# powerlolu.net
KiCad netlist of a schematic drawn in EAGLE
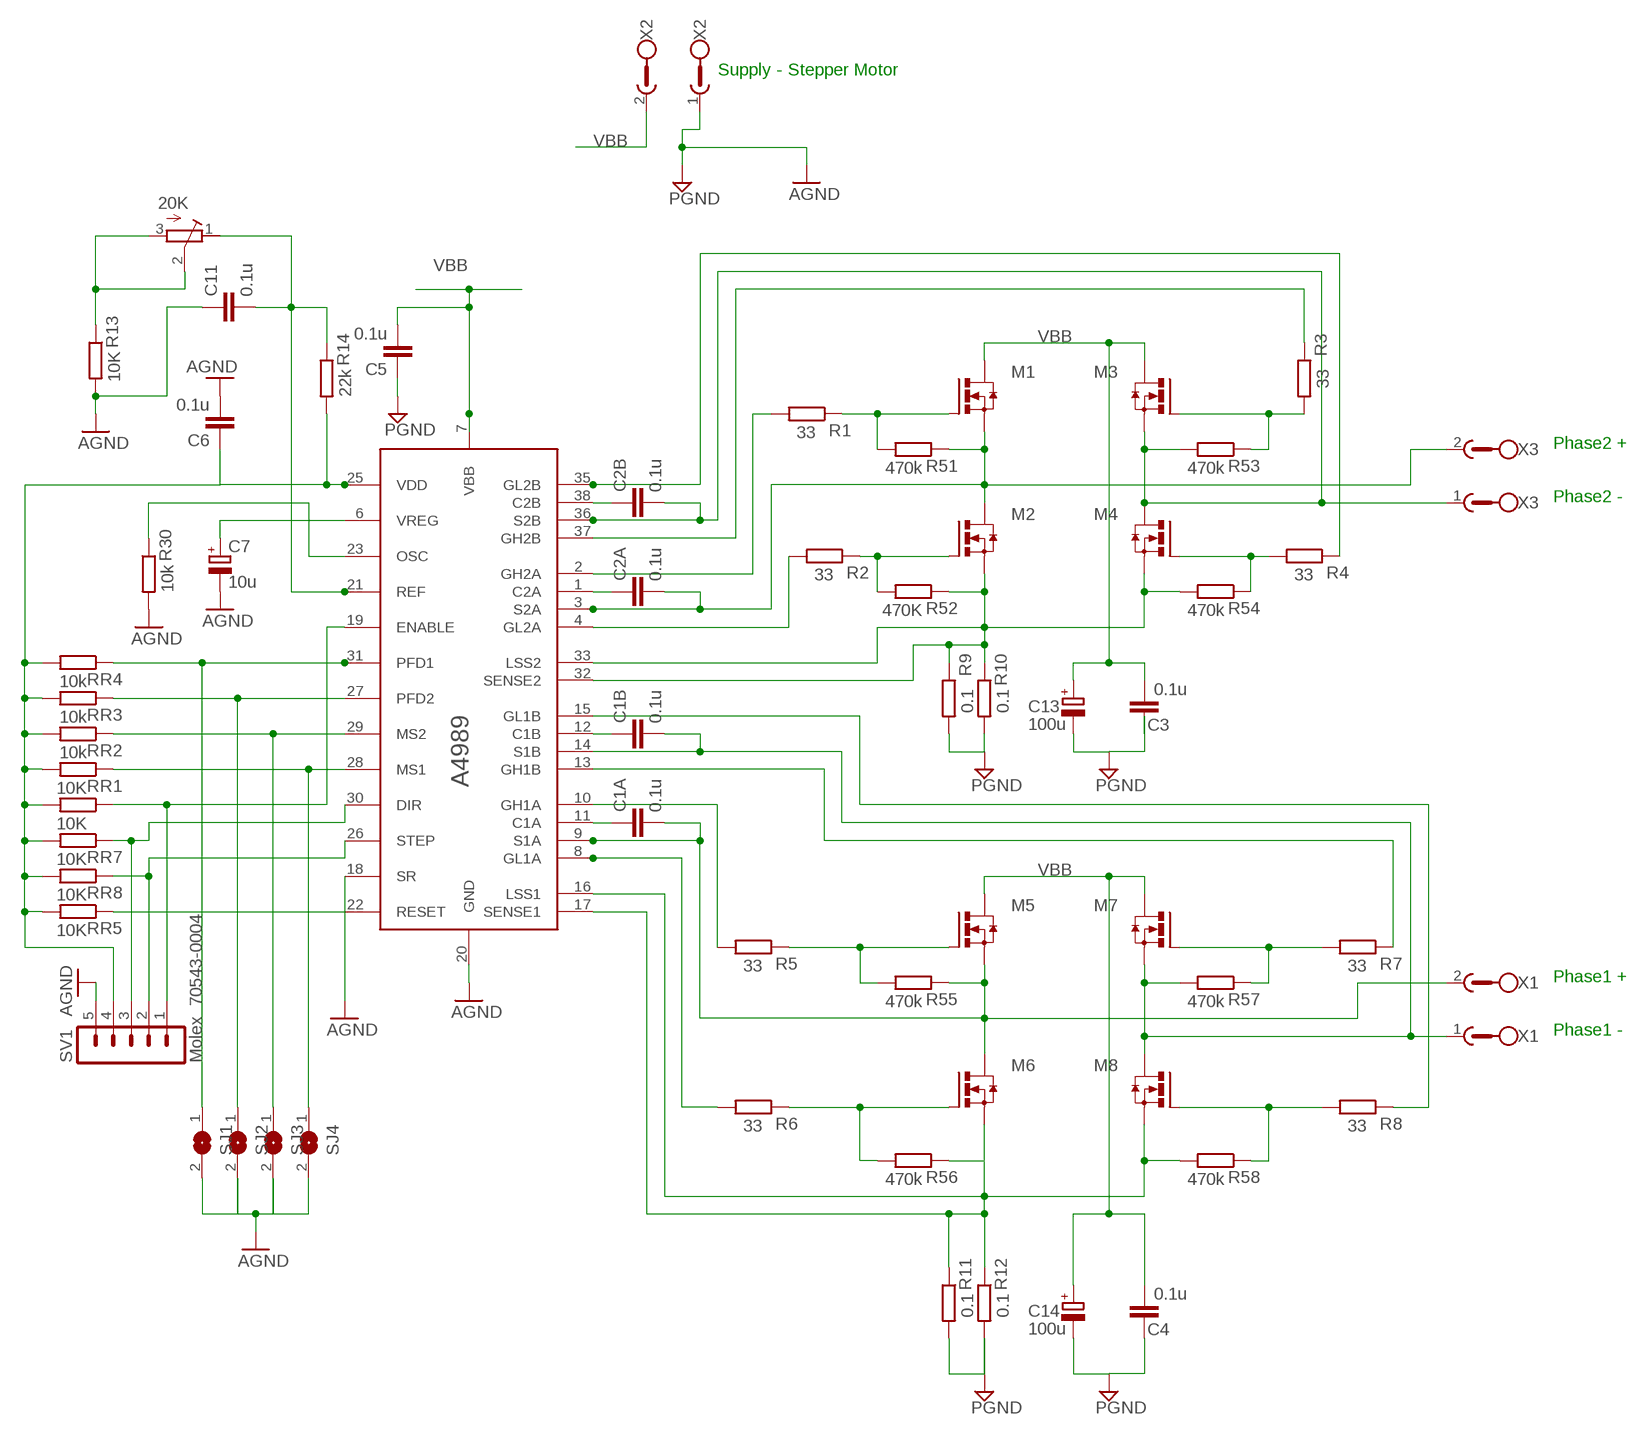
[diagram p0: schematic, sheet 1]

(export (version "E")
  (design (tool "Eeschema 10.0.6"))
  (components
    (comp (ref "A4989")
      (value "A4989")
      (footprint "eagle-import:TSSOP39")
      (libsource (lib "eagle-import") (part "A4989"))
    )
    (comp (ref "C1A")
      (value "0.1u")
      (footprint "eagle-import:C0603")
      (libsource (lib "eagle-import") (part "C-EUC0603"))
    )
    (comp (ref "C1B")
      (value "0.1u")
      (footprint "eagle-import:C0603")
      (libsource (lib "eagle-import") (part "C-EUC0603"))
    )
    (comp (ref "C2A")
      (value "0.1u")
      (footprint "eagle-import:C0603")
      (libsource (lib "eagle-import") (part "C-EUC0603"))
    )
    (comp (ref "C2B")
      (value "0.1u")
      (footprint "eagle-import:C0603")
      (libsource (lib "eagle-import") (part "C-EUC0603"))
    )
    (comp (ref "C3")
      (value "0.1u")
      (footprint "eagle-import:C0603")
      (libsource (lib "eagle-import") (part "C-EUC0603"))
    )
    (comp (ref "C4")
      (value "0.1u")
      (footprint "eagle-import:C0603")
      (libsource (lib "eagle-import") (part "C-EUC0603"))
    )
    (comp (ref "C5")
      (value "0.1u")
      (footprint "eagle-import:C0603")
      (libsource (lib "eagle-import") (part "C-EUC0603"))
    )
    (comp (ref "C6")
      (value "0.1u")
      (footprint "eagle-import:C0603")
      (libsource (lib "eagle-import") (part "C-EUC0603"))
    )
    (comp (ref "C7")
      (value "10u")
      (footprint "eagle-import:153CLV-0605")
      (libsource (lib "eagle-import") (part "CPOL-EU153CLV-0605"))
    )
    (comp (ref "C11")
      (value "0.1u")
      (footprint "eagle-import:C0603")
      (libsource (lib "eagle-import") (part "C-EUC0603"))
    )
    (comp (ref "C13")
      (value "100u")
      (footprint "eagle-import:E5-10,5")
      (libsource (lib "eagle-import") (part "CPOL-EUE5-10.5"))
    )
    (comp (ref "C14")
      (value "100u")
      (footprint "eagle-import:E5-10,5")
      (libsource (lib "eagle-import") (part "CPOL-EUE5-10.5"))
    )
    (comp (ref "M1")
      (value "IRLR024N")
      (footprint "eagle-import:TO252")
      (libsource (lib "eagle-import") (part "IRLR024N"))
    )
    (comp (ref "M2")
      (value "IRLR024N")
      (footprint "eagle-import:TO252")
      (libsource (lib "eagle-import") (part "IRLR024N"))
    )
    (comp (ref "M3")
      (value "IRLR024N")
      (footprint "eagle-import:TO252")
      (libsource (lib "eagle-import") (part "IRLR024N"))
    )
    (comp (ref "M4")
      (value "IRLR024N")
      (footprint "eagle-import:TO252")
      (libsource (lib "eagle-import") (part "IRLR024N"))
    )
    (comp (ref "M5")
      (value "IRLR024N")
      (footprint "eagle-import:TO252")
      (libsource (lib "eagle-import") (part "IRLR024N"))
    )
    (comp (ref "M6")
      (value "IRLR024N")
      (footprint "eagle-import:TO252")
      (libsource (lib "eagle-import") (part "IRLR024N"))
    )
    (comp (ref "M7")
      (value "IRLR024N")
      (footprint "eagle-import:TO252")
      (libsource (lib "eagle-import") (part "IRLR024N"))
    )
    (comp (ref "M8")
      (value "IRLR024N")
      (footprint "eagle-import:TO252")
      (libsource (lib "eagle-import") (part "IRLR024N"))
    )
    (comp (ref "R1")
      (value "33")
      (footprint "eagle-import:R0603")
      (libsource (lib "eagle-import") (part "R-EU_R0603"))
    )
    (comp (ref "R2")
      (value "33")
      (footprint "eagle-import:R0603")
      (libsource (lib "eagle-import") (part "R-EU_R0603"))
    )
    (comp (ref "R3")
      (value "33")
      (footprint "eagle-import:R0603")
      (libsource (lib "eagle-import") (part "R-EU_R0603"))
    )
    (comp (ref "R4")
      (value "33")
      (footprint "eagle-import:R0603")
      (libsource (lib "eagle-import") (part "R-EU_R0603"))
    )
    (comp (ref "R5")
      (value "33")
      (footprint "eagle-import:R0603")
      (libsource (lib "eagle-import") (part "R-EU_R0603"))
    )
    (comp (ref "R6")
      (value "33")
      (footprint "eagle-import:R0603")
      (libsource (lib "eagle-import") (part "R-EU_R0603"))
    )
    (comp (ref "R7")
      (value "33")
      (footprint "eagle-import:R0603")
      (libsource (lib "eagle-import") (part "R-EU_R0603"))
    )
    (comp (ref "R8")
      (value "33")
      (footprint "eagle-import:R0603")
      (libsource (lib "eagle-import") (part "R-EU_R0603"))
    )
    (comp (ref "R9")
      (value "0.1")
      (footprint "eagle-import:R2512")
      (libsource (lib "eagle-import") (part "R-EU_R2512"))
    )
    (comp (ref "R10")
      (value "0.1")
      (footprint "eagle-import:R2512")
      (libsource (lib "eagle-import") (part "R-EU_R2512"))
    )
    (comp (ref "R11")
      (value "0.1")
      (footprint "eagle-import:R2512")
      (libsource (lib "eagle-import") (part "R-EU_R2512"))
    )
    (comp (ref "R12")
      (value "0.1")
      (footprint "eagle-import:R2512")
      (libsource (lib "eagle-import") (part "R-EU_R2512"))
    )
    (comp (ref "R13")
      (value "10K")
      (footprint "eagle-import:R0603")
      (libsource (lib "eagle-import") (part "R-EU_R0603"))
    )
    (comp (ref "R14")
      (value "22k")
      (footprint "eagle-import:R0603")
      (libsource (lib "eagle-import") (part "R-EU_R0603"))
    )
    (comp (ref "R30")
      (value "10k")
      (footprint "eagle-import:R0603")
      (libsource (lib "eagle-import") (part "R-EU_R0603"))
    )
    (comp (ref "R51")
      (value "470k")
      (footprint "eagle-import:R0603")
      (libsource (lib "eagle-import") (part "R-EU_R0603"))
    )
    (comp (ref "R52")
      (value "470K")
      (footprint "eagle-import:R0603")
      (libsource (lib "eagle-import") (part "R-EU_R0603"))
    )
    (comp (ref "R53")
      (value "470k")
      (footprint "eagle-import:R0603")
      (libsource (lib "eagle-import") (part "R-EU_R0603"))
    )
    (comp (ref "R54")
      (value "470k")
      (footprint "eagle-import:R0603")
      (libsource (lib "eagle-import") (part "R-EU_R0603"))
    )
    (comp (ref "R55")
      (value "470k")
      (footprint "eagle-import:R0603")
      (libsource (lib "eagle-import") (part "R-EU_R0603"))
    )
    (comp (ref "R56")
      (value "470k")
      (footprint "eagle-import:R0603")
      (libsource (lib "eagle-import") (part "R-EU_R0603"))
    )
    (comp (ref "R57")
      (value "470k")
      (footprint "eagle-import:R0603")
      (libsource (lib "eagle-import") (part "R-EU_R0603"))
    )
    (comp (ref "R58")
      (value "470k")
      (footprint "eagle-import:R0603")
      (libsource (lib "eagle-import") (part "R-EU_R0603"))
    )
    (comp (ref "RR1")
      (value "10K")
      (footprint "eagle-import:R0603")
      (libsource (lib "eagle-import") (part "R-EU_R0603"))
    )
    (comp (ref "RR2")
      (value "10k")
      (footprint "eagle-import:R0603")
      (libsource (lib "eagle-import") (part "R-EU_R0603"))
    )
    (comp (ref "RR3")
      (value "10k")
      (footprint "eagle-import:R0603")
      (libsource (lib "eagle-import") (part "R-EU_R0603"))
    )
    (comp (ref "RR4")
      (value "10k")
      (footprint "eagle-import:R0603")
      (libsource (lib "eagle-import") (part "R-EU_R0603"))
    )
    (comp (ref "RR5")
      (value "10K")
      (footprint "eagle-import:R0603")
      (libsource (lib "eagle-import") (part "R-EU_R0603"))
    )
    (comp (ref "RR6")
      (value "10K")
      (footprint "eagle-import:R0603")
      (libsource (lib "eagle-import") (part "R-EU_R0603"))
    )
    (comp (ref "RR7")
      (value "10K")
      (footprint "eagle-import:R0603")
      (libsource (lib "eagle-import") (part "R-EU_R0603"))
    )
    (comp (ref "RR8")
      (value "10K")
      (footprint "eagle-import:R0603")
      (libsource (lib "eagle-import") (part "R-EU_R0603"))
    )
    (comp (ref "SJ1") (value "SJ") (footprint "eagle-import:SJ") (libsource (lib "eagle-import") (part "SJ")))
    (comp (ref "SJ2") (value "SJ") (footprint "eagle-import:SJ") (libsource (lib "eagle-import") (part "SJ")))
    (comp (ref "SJ3") (value "SJ") (footprint "eagle-import:SJ") (libsource (lib "eagle-import") (part "SJ")))
    (comp (ref "SJ4") (value "SJ") (footprint "eagle-import:SJ") (libsource (lib "eagle-import") (part "SJ")))
    (comp (ref "SV1")
      (value "Molex 70543-0004")
      (footprint "eagle-import:MA05-1")
      (libsource (lib "eagle-import") (part "MA05-1"))
    )
    (comp (ref "U$1")
      (value "20K")
      (footprint "eagle-import:BOURNS_3266W")
      (libsource (lib "eagle-import") (part "BOURNS_TRIMMER_3266W"))
    )
    (comp (ref "X1")
      (value "GMGDS32")
      (footprint "eagle-import:GMKDS32")
      (libsource (lib "eagle-import") (part "GMGDS32"))
    )
    (comp (ref "X2")
      (value "GMGDS32")
      (footprint "eagle-import:GMKDS32")
      (libsource (lib "eagle-import") (part "GMGDS32"))
    )
    (comp (ref "X3")
      (value "GMGDS32")
      (footprint "eagle-import:GMKDS32")
      (libsource (lib "eagle-import") (part "GMGDS32"))
    )
  )
  (nets
    (net (code "1") (name "/VBB") (class "Default")
      (node (ref "A4989") (pin "7") (pinfunction "VBB_7") (pintype "bidirectional"))
      (node (ref "C13") (pin "+") (pinfunction "+_+") (pintype "passive"))
      (node (ref "C14") (pin "+") (pinfunction "+_+") (pintype "passive"))
      (node (ref "C3") (pin "2") (pinfunction "2_2") (pintype "passive"))
      (node (ref "C4") (pin "2") (pinfunction "2_2") (pintype "passive"))
      (node (ref "C5") (pin "2") (pinfunction "2_2") (pintype "passive"))
      (node (ref "M1") (pin "3") (pinfunction "D_3") (pintype "passive"))
      (node (ref "M3") (pin "3") (pinfunction "D_3") (pintype "passive"))
      (node (ref "M5") (pin "3") (pinfunction "D_3") (pintype "passive"))
      (node (ref "M7") (pin "3") (pinfunction "D_3") (pintype "passive"))
      (node (ref "X2") (pin "2") (pinfunction "2_2") (pintype "passive"))
    )
    (net (code "2") (name "AGND") (class "Default")
      (node (ref "A4989") (pin "18") (pinfunction "SR_18") (pintype "bidirectional"))
      (node (ref "A4989") (pin "20") (pinfunction "GND_20") (pintype "bidirectional"))
      (node (ref "C11") (pin "1") (pinfunction "1_1") (pintype "passive"))
      (node (ref "C13") (pin "-") (pinfunction "-_-") (pintype "passive"))
      (node (ref "C14") (pin "-") (pinfunction "-_-") (pintype "passive"))
      (node (ref "C3") (pin "1") (pinfunction "1_1") (pintype "passive"))
      (node (ref "C4") (pin "1") (pinfunction "1_1") (pintype "passive"))
      (node (ref "C5") (pin "1") (pinfunction "1_1") (pintype "passive"))
      (node (ref "C6") (pin "2") (pinfunction "2_2") (pintype "passive"))
      (node (ref "C7") (pin "-") (pinfunction "-_-") (pintype "passive"))
      (node (ref "R10") (pin "2") (pinfunction "2_2") (pintype "passive"))
      (node (ref "R11") (pin "2") (pinfunction "2_2") (pintype "passive"))
      (node (ref "R12") (pin "2") (pinfunction "2_2") (pintype "passive"))
      (node (ref "R13") (pin "2") (pinfunction "2_2") (pintype "passive"))
      (node (ref "R30") (pin "2") (pinfunction "2_2") (pintype "passive"))
      (node (ref "R9") (pin "2") (pinfunction "2_2") (pintype "passive"))
      (node (ref "SJ1") (pin "2") (pinfunction "2_2") (pintype "passive"))
      (node (ref "SJ2") (pin "2") (pinfunction "2_2") (pintype "passive"))
      (node (ref "SJ3") (pin "2") (pinfunction "2_2") (pintype "passive"))
      (node (ref "SJ4") (pin "2") (pinfunction "2_2") (pintype "passive"))
      (node (ref "SV1") (pin "5") (pinfunction "5_5") (pintype "passive"))
      (node (ref "X2") (pin "1") (pinfunction "1_1") (pintype "passive"))
    )
    (net (code "3") (name "Net-(A4989-C1A)") (class "Default")
      (node (ref "A4989") (pin "11") (pinfunction "C1A_11") (pintype "bidirectional"))
      (node (ref "C1A") (pin "1") (pinfunction "1_1") (pintype "passive"))
    )
    (net (code "4") (name "Net-(A4989-C1B)") (class "Default")
      (node (ref "A4989") (pin "12") (pinfunction "C1B_12") (pintype "bidirectional"))
      (node (ref "C1B") (pin "1") (pinfunction "1_1") (pintype "passive"))
    )
    (net (code "5") (name "Net-(A4989-C2A)") (class "Default")
      (node (ref "A4989") (pin "1") (pinfunction "C2A_1") (pintype "bidirectional"))
      (node (ref "C2A") (pin "1") (pinfunction "1_1") (pintype "passive"))
    )
    (net (code "6") (name "Net-(A4989-C2B)") (class "Default")
      (node (ref "A4989") (pin "38") (pinfunction "C2B_38") (pintype "bidirectional"))
      (node (ref "C2B") (pin "1") (pinfunction "1_1") (pintype "passive"))
    )
    (net (code "7") (name "Net-(A4989-DIR)") (class "Default")
      (node (ref "A4989") (pin "30") (pinfunction "DIR_30") (pintype "bidirectional"))
      (node (ref "RR7") (pin "1") (pinfunction "1_1") (pintype "passive"))
      (node (ref "SV1") (pin "3") (pinfunction "3_3") (pintype "passive"))
    )
    (net (code "8") (name "Net-(A4989-ENABLE)") (class "Default")
      (node (ref "A4989") (pin "19") (pinfunction "ENABLE_19") (pintype "bidirectional"))
      (node (ref "RR6") (pin "1") (pinfunction "1_1") (pintype "passive"))
      (node (ref "SV1") (pin "1") (pinfunction "1_1") (pintype "passive"))
    )
    (net (code "9") (name "Net-(A4989-GH1A)") (class "Default")
      (node (ref "A4989") (pin "10") (pinfunction "GH1A_10") (pintype "bidirectional"))
      (node (ref "R5") (pin "2") (pinfunction "2_2") (pintype "passive"))
    )
    (net (code "10") (name "Net-(A4989-GH1B)") (class "Default")
      (node (ref "A4989") (pin "13") (pinfunction "GH1B_13") (pintype "bidirectional"))
      (node (ref "R7") (pin "1") (pinfunction "1_1") (pintype "passive"))
    )
    (net (code "11") (name "Net-(A4989-GH2A)") (class "Default")
      (node (ref "A4989") (pin "2") (pinfunction "GH2A_2") (pintype "bidirectional"))
      (node (ref "R1") (pin "2") (pinfunction "2_2") (pintype "passive"))
    )
    (net (code "12") (name "Net-(A4989-GH2B)") (class "Default")
      (node (ref "A4989") (pin "37") (pinfunction "GH2B_37") (pintype "bidirectional"))
      (node (ref "R3") (pin "1") (pinfunction "1_1") (pintype "passive"))
    )
    (net (code "13") (name "Net-(A4989-GL1A)") (class "Default")
      (node (ref "A4989") (pin "8") (pinfunction "GL1A_8") (pintype "bidirectional"))
      (node (ref "R6") (pin "2") (pinfunction "2_2") (pintype "passive"))
    )
    (net (code "14") (name "Net-(A4989-GL1B)") (class "Default")
      (node (ref "A4989") (pin "15") (pinfunction "GL1B_15") (pintype "bidirectional"))
      (node (ref "R8") (pin "1") (pinfunction "1_1") (pintype "passive"))
    )
    (net (code "15") (name "Net-(A4989-GL2A)") (class "Default")
      (node (ref "A4989") (pin "4") (pinfunction "GL2A_4") (pintype "bidirectional"))
      (node (ref "R2") (pin "2") (pinfunction "2_2") (pintype "passive"))
    )
    (net (code "16") (name "Net-(A4989-GL2B)") (class "Default")
      (node (ref "A4989") (pin "35") (pinfunction "GL2B_35") (pintype "bidirectional"))
      (node (ref "R4") (pin "1") (pinfunction "1_1") (pintype "passive"))
    )
    (net (code "17") (name "Net-(A4989-LSS1)") (class "Default")
      (node (ref "A4989") (pin "16") (pinfunction "LSS1_16") (pintype "bidirectional"))
      (node (ref "A4989") (pin "17") (pinfunction "SENSE1_17") (pintype "bidirectional"))
      (node (ref "M6") (pin "2") (pinfunction "S_2") (pintype "passive"))
      (node (ref "M8") (pin "2") (pinfunction "S_2") (pintype "passive"))
      (node (ref "R11") (pin "1") (pinfunction "1_1") (pintype "passive"))
      (node (ref "R12") (pin "1") (pinfunction "1_1") (pintype "passive"))
      (node (ref "R56") (pin "1") (pinfunction "1_1") (pintype "passive"))
      (node (ref "R58") (pin "2") (pinfunction "2_2") (pintype "passive"))
    )
    (net (code "18") (name "Net-(A4989-LSS2)") (class "Default")
      (node (ref "A4989") (pin "32") (pinfunction "SENSE2_32") (pintype "bidirectional"))
      (node (ref "A4989") (pin "33") (pinfunction "LSS2_33") (pintype "bidirectional"))
      (node (ref "M2") (pin "2") (pinfunction "S_2") (pintype "passive"))
      (node (ref "M4") (pin "2") (pinfunction "S_2") (pintype "passive"))
      (node (ref "R10") (pin "1") (pinfunction "1_1") (pintype "passive"))
      (node (ref "R52") (pin "1") (pinfunction "1_1") (pintype "passive"))
      (node (ref "R54") (pin "2") (pinfunction "2_2") (pintype "passive"))
      (node (ref "R9") (pin "1") (pinfunction "1_1") (pintype "passive"))
    )
    (net (code "19") (name "Net-(A4989-MS1)") (class "Default")
      (node (ref "A4989") (pin "28") (pinfunction "MS1_28") (pintype "bidirectional"))
      (node (ref "RR1") (pin "1") (pinfunction "1_1") (pintype "passive"))
      (node (ref "SJ4") (pin "1") (pinfunction "1_1") (pintype "passive"))
    )
    (net (code "20") (name "Net-(A4989-MS2)") (class "Default")
      (node (ref "A4989") (pin "29") (pinfunction "MS2_29") (pintype "bidirectional"))
      (node (ref "RR2") (pin "1") (pinfunction "1_1") (pintype "passive"))
      (node (ref "SJ3") (pin "1") (pinfunction "1_1") (pintype "passive"))
    )
    (net (code "21") (name "Net-(A4989-OSC)") (class "Default")
      (node (ref "A4989") (pin "23") (pinfunction "OSC_23") (pintype "bidirectional"))
      (node (ref "R30") (pin "1") (pinfunction "1_1") (pintype "passive"))
    )
    (net (code "22") (name "Net-(A4989-PFD1)") (class "Default")
      (node (ref "A4989") (pin "31") (pinfunction "PFD1_31") (pintype "bidirectional"))
      (node (ref "RR4") (pin "1") (pinfunction "1_1") (pintype "passive"))
      (node (ref "SJ1") (pin "1") (pinfunction "1_1") (pintype "passive"))
    )
    (net (code "23") (name "Net-(A4989-PFD2)") (class "Default")
      (node (ref "A4989") (pin "27") (pinfunction "PFD2_27") (pintype "bidirectional"))
      (node (ref "RR3") (pin "1") (pinfunction "1_1") (pintype "passive"))
      (node (ref "SJ2") (pin "1") (pinfunction "1_1") (pintype "passive"))
    )
    (net (code "24") (name "Net-(A4989-REF)") (class "Default")
      (node (ref "A4989") (pin "21") (pinfunction "REF_21") (pintype "bidirectional"))
      (node (ref "C11") (pin "2") (pinfunction "2_2") (pintype "passive"))
      (node (ref "R14") (pin "1") (pinfunction "1_1") (pintype "passive"))
      (node (ref "U$1") (pin "1") (pinfunction "A_1") (pintype "passive"))
    )
    (net (code "25") (name "Net-(A4989-RESET)") (class "Default")
      (node (ref "A4989") (pin "22") (pinfunction "RESET_22") (pintype "bidirectional"))
      (node (ref "RR5") (pin "1") (pinfunction "1_1") (pintype "passive"))
    )
    (net (code "26") (name "Net-(A4989-S1A)") (class "Default")
      (node (ref "A4989") (pin "9") (pinfunction "S1A_9") (pintype "bidirectional"))
      (node (ref "C1A") (pin "2") (pinfunction "2_2") (pintype "passive"))
      (node (ref "M5") (pin "2") (pinfunction "S_2") (pintype "passive"))
      (node (ref "M6") (pin "3") (pinfunction "D_3") (pintype "passive"))
      (node (ref "R55") (pin "1") (pinfunction "1_1") (pintype "passive"))
      (node (ref "X1") (pin "2") (pinfunction "2_2") (pintype "passive"))
    )
    (net (code "27") (name "Net-(A4989-S1B)") (class "Default")
      (node (ref "A4989") (pin "14") (pinfunction "S1B_14") (pintype "bidirectional"))
      (node (ref "C1B") (pin "2") (pinfunction "2_2") (pintype "passive"))
      (node (ref "M7") (pin "2") (pinfunction "S_2") (pintype "passive"))
      (node (ref "M8") (pin "3") (pinfunction "D_3") (pintype "passive"))
      (node (ref "R57") (pin "2") (pinfunction "2_2") (pintype "passive"))
      (node (ref "X1") (pin "1") (pinfunction "1_1") (pintype "passive"))
    )
    (net (code "28") (name "Net-(A4989-S2A)") (class "Default")
      (node (ref "A4989") (pin "3") (pinfunction "S2A_3") (pintype "bidirectional"))
      (node (ref "C2A") (pin "2") (pinfunction "2_2") (pintype "passive"))
      (node (ref "M1") (pin "2") (pinfunction "S_2") (pintype "passive"))
      (node (ref "M2") (pin "3") (pinfunction "D_3") (pintype "passive"))
      (node (ref "R51") (pin "1") (pinfunction "1_1") (pintype "passive"))
      (node (ref "X3") (pin "2") (pinfunction "2_2") (pintype "passive"))
    )
    (net (code "29") (name "Net-(A4989-S2B)") (class "Default")
      (node (ref "A4989") (pin "36") (pinfunction "S2B_36") (pintype "bidirectional"))
      (node (ref "C2B") (pin "2") (pinfunction "2_2") (pintype "passive"))
      (node (ref "M3") (pin "2") (pinfunction "S_2") (pintype "passive"))
      (node (ref "M4") (pin "3") (pinfunction "D_3") (pintype "passive"))
      (node (ref "R53") (pin "2") (pinfunction "2_2") (pintype "passive"))
      (node (ref "X3") (pin "1") (pinfunction "1_1") (pintype "passive"))
    )
    (net (code "30") (name "Net-(A4989-STEP)") (class "Default")
      (node (ref "A4989") (pin "26") (pinfunction "STEP_26") (pintype "bidirectional"))
      (node (ref "RR8") (pin "1") (pinfunction "1_1") (pintype "passive"))
      (node (ref "SV1") (pin "2") (pinfunction "2_2") (pintype "passive"))
    )
    (net (code "31") (name "Net-(A4989-VDD)") (class "Default")
      (node (ref "A4989") (pin "25") (pinfunction "VDD_25") (pintype "bidirectional"))
      (node (ref "C6") (pin "1") (pinfunction "1_1") (pintype "passive"))
      (node (ref "R14") (pin "2") (pinfunction "2_2") (pintype "passive"))
      (node (ref "RR1") (pin "2") (pinfunction "2_2") (pintype "passive"))
      (node (ref "RR2") (pin "2") (pinfunction "2_2") (pintype "passive"))
      (node (ref "RR3") (pin "2") (pinfunction "2_2") (pintype "passive"))
      (node (ref "RR4") (pin "2") (pinfunction "2_2") (pintype "passive"))
      (node (ref "RR5") (pin "2") (pinfunction "2_2") (pintype "passive"))
      (node (ref "RR6") (pin "2") (pinfunction "2_2") (pintype "passive"))
      (node (ref "RR7") (pin "2") (pinfunction "2_2") (pintype "passive"))
      (node (ref "RR8") (pin "2") (pinfunction "2_2") (pintype "passive"))
      (node (ref "SV1") (pin "4") (pinfunction "4_4") (pintype "passive"))
    )
    (net (code "32") (name "Net-(A4989-VREG)") (class "Default")
      (node (ref "A4989") (pin "6") (pinfunction "VREG_6") (pintype "bidirectional"))
      (node (ref "C7") (pin "+") (pinfunction "+_+") (pintype "passive"))
    )
    (net (code "33") (name "Net-(M1-G)") (class "Default")
      (node (ref "M1") (pin "1") (pinfunction "G_1") (pintype "passive"))
      (node (ref "R1") (pin "1") (pinfunction "1_1") (pintype "passive"))
      (node (ref "R51") (pin "2") (pinfunction "2_2") (pintype "passive"))
    )
    (net (code "34") (name "Net-(M2-G)") (class "Default")
      (node (ref "M2") (pin "1") (pinfunction "G_1") (pintype "passive"))
      (node (ref "R2") (pin "1") (pinfunction "1_1") (pintype "passive"))
      (node (ref "R52") (pin "2") (pinfunction "2_2") (pintype "passive"))
    )
    (net (code "35") (name "Net-(M3-G)") (class "Default")
      (node (ref "M3") (pin "1") (pinfunction "G_1") (pintype "passive"))
      (node (ref "R3") (pin "2") (pinfunction "2_2") (pintype "passive"))
      (node (ref "R53") (pin "1") (pinfunction "1_1") (pintype "passive"))
    )
    (net (code "36") (name "Net-(M4-G)") (class "Default")
      (node (ref "M4") (pin "1") (pinfunction "G_1") (pintype "passive"))
      (node (ref "R4") (pin "2") (pinfunction "2_2") (pintype "passive"))
      (node (ref "R54") (pin "1") (pinfunction "1_1") (pintype "passive"))
    )
    (net (code "37") (name "Net-(M5-G)") (class "Default")
      (node (ref "M5") (pin "1") (pinfunction "G_1") (pintype "passive"))
      (node (ref "R5") (pin "1") (pinfunction "1_1") (pintype "passive"))
      (node (ref "R55") (pin "2") (pinfunction "2_2") (pintype "passive"))
    )
    (net (code "38") (name "Net-(M6-G)") (class "Default")
      (node (ref "M6") (pin "1") (pinfunction "G_1") (pintype "passive"))
      (node (ref "R56") (pin "2") (pinfunction "2_2") (pintype "passive"))
      (node (ref "R6") (pin "1") (pinfunction "1_1") (pintype "passive"))
    )
    (net (code "39") (name "Net-(M7-G)") (class "Default")
      (node (ref "M7") (pin "1") (pinfunction "G_1") (pintype "passive"))
      (node (ref "R57") (pin "1") (pinfunction "1_1") (pintype "passive"))
      (node (ref "R7") (pin "2") (pinfunction "2_2") (pintype "passive"))
    )
    (net (code "40") (name "Net-(M8-G)") (class "Default")
      (node (ref "M8") (pin "1") (pinfunction "G_1") (pintype "passive"))
      (node (ref "R58") (pin "1") (pinfunction "1_1") (pintype "passive"))
      (node (ref "R8") (pin "2") (pinfunction "2_2") (pintype "passive"))
    )
    (net (code "41") (name "Net-(U$1-E)") (class "Default")
      (node (ref "R13") (pin "1") (pinfunction "1_1") (pintype "passive"))
      (node (ref "U$1") (pin "2") (pinfunction "S_2") (pintype "passive"))
      (node (ref "U$1") (pin "3") (pinfunction "E_3") (pintype "passive"))
    )
  )
)
